# lb-charDisp-SMPS5V.net
KiCad netlist of a schematic drawn in Altium Designer
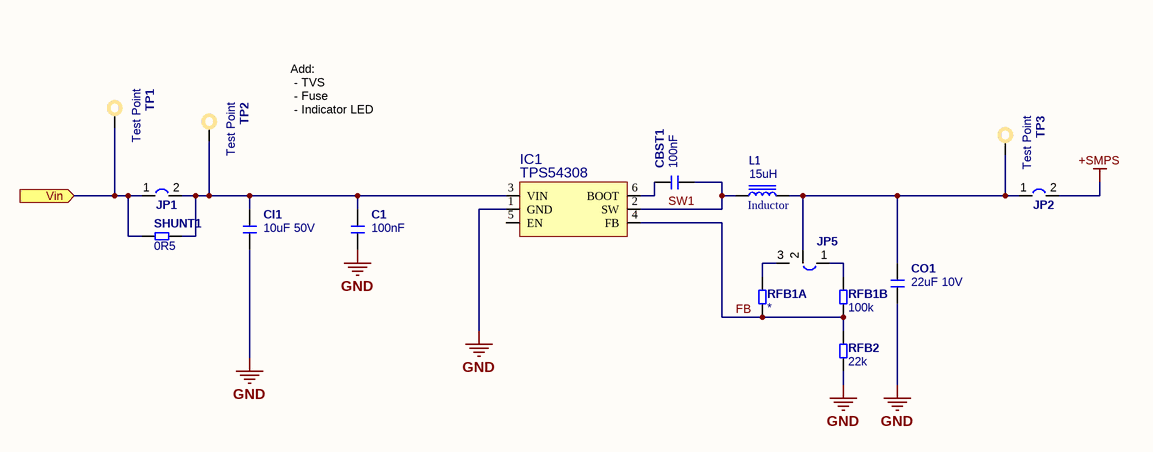
[diagram p0: lb-charDisp-SMPS5V.SchDoc]

(export (version "E")
  (design (tool "Eeschema 10.0.6"))
  (components
    (comp (ref "C1")
      (value "100nF")
      (footprint "C0603_N")
      (description "Capacitor MLCC")
      (fields
        (field (name "MANUFACTURER") "Yageo")
        (field (name "MANUFACTURER PART NUMBER") "CC0603KRX7R9BB104")
      )
      (libsource (lib "wes") (part "Capacitor"))
    )
    (comp (ref "CBST1")
      (value "100nF")
      (footprint "C0603_N")
      (description "Capacitor MLCC")
      (fields
        (field (name "MANUFACTURER") "Yageo")
        (field (name "MANUFACTURER PART NUMBER") "CC0603KRX7R9BB104")
      )
      (libsource (lib "wes") (part "Capacitor"))
    )
    (comp (ref "CI1")
      (value "10uF 50V")
      (footprint "C1210_N")
      (description "Capacitor MLCC")
      (fields
        (field (name "MANUFACTURER") "Yageo")
        (field (name "MANUFACTURER PART NUMBER") "CC0603KRX7R9BB104")
      )
      (libsource (lib "wes") (part "Capacitor"))
    )
    (comp (ref "CO1")
      (value "22uF 10V")
      (footprint "C1210_N")
      (description "Capacitor MLCC")
      (fields
        (field (name "MANUFACTURER") "Yageo")
        (field (name "MANUFACTURER PART NUMBER") "CC0603KRX7R9BB104")
      )
      (libsource (lib "wes") (part "Capacitor"))
    )
    (comp (ref "IC1")
      (value "TPS54308")
      (footprint "SOT23")
      (description "Buck Converter")
      (libsource (lib "wes") (part "TPS54308"))
    )
    (comp (ref "JP1")
      (value "Jumper 2W")
      (footprint "Jumper SMD 2W NO")
      (libsource (lib "wes") (part "Jumper 2W"))
    )
    (comp (ref "JP2")
      (value "Jumper 2W")
      (footprint "Jumper SMD 2W NO")
      (libsource (lib "wes") (part "Jumper 2W"))
    )
    (comp (ref "JP5")
      (value "Jumper 3W")
      (footprint "Jumper SMD 3W NO")
      (libsource (lib "wes") (part "Jumper 3W"))
    )
    (comp (ref "L1")
      (value "Inductor")
      (footprint "Inductor 4mm")
      (fields (field (name "ALTIUM_VALUE") "15uH"))
      (libsource (lib "wes") (part "Inductor"))
    )
    (comp (ref "RFB1A")
      (value "*")
      (footprint "R0603")
      (fields (field (name "ALTIUM_VALUE") "*") (field (name "PUBLISHER") "Altium Limited"))
      (libsource (lib "wes") (part "Resistor"))
    )
    (comp (ref "RFB1B")
      (value "100k")
      (footprint "R0603")
      (fields (field (name "PUBLISHER") "Altium Limited"))
      (libsource (lib "wes") (part "Resistor"))
    )
    (comp (ref "RFB2")
      (value "22k")
      (footprint "R0603")
      (fields (field (name "PUBLISHER") "Altium Limited"))
      (libsource (lib "wes") (part "Resistor"))
    )
    (comp (ref "SHUNT1")
      (value "0R5")
      (footprint "R0603")
      (fields (field (name "PUBLISHER") "Altium Limited"))
      (libsource (lib "wes") (part "Resistor"))
    )
    (comp (ref "TP1")
      (value "Test Point")
      (footprint "TestPoint-1.2mm")
      (libsource (lib "wes") (part "Test Point"))
    )
    (comp (ref "TP2")
      (value "Test Point")
      (footprint "TestPoint-1.2mm")
      (libsource (lib "wes") (part "Test Point"))
    )
    (comp (ref "TP3")
      (value "Test Point")
      (footprint "TestPoint-1.2mm")
      (libsource (lib "wes") (part "Test Point"))
    )
  )
  (nets
    (net (code "1") (name "+SMPS") (class "Default")
      (node (ref "JP2") (pin "2") (pinfunction "2_2") (pintype "passive"))
    )
    (net (code "2") (name "/FB") (class "Default")
      (node (ref "IC1") (pin "4") (pinfunction "FB_4") (pintype "passive"))
      (node (ref "RFB1A") (pin "1") (pinfunction "1_1") (pintype "passive"))
      (node (ref "RFB1B") (pin "1") (pinfunction "1_1") (pintype "passive"))
      (node (ref "RFB2") (pin "2") (pinfunction "2_2") (pintype "passive"))
    )
    (net (code "3") (name "/SW1") (class "Default")
      (node (ref "CBST1") (pin "2") (pintype "passive"))
      (node (ref "IC1") (pin "2") (pinfunction "SW_2") (pintype "passive"))
      (node (ref "L1") (pin "1") (pinfunction "1_1") (pintype "passive"))
    )
    (net (code "4") (name "/Vin") (class "Default")
      (node (ref "JP1") (pin "1") (pinfunction "1_1") (pintype "passive"))
      (node (ref "SHUNT1") (pin "1") (pinfunction "1_1") (pintype "passive"))
      (node (ref "TP1") (pin "1") (pinfunction "1_1") (pintype "passive"))
    )
    (net (code "5") (name "GND") (class "Default")
      (node (ref "C1") (pin "2") (pintype "passive"))
      (node (ref "CI1") (pin "2") (pintype "passive"))
      (node (ref "CO1") (pin "2") (pintype "passive"))
      (node (ref "IC1") (pin "1") (pinfunction "GND_1") (pintype "passive"))
      (node (ref "RFB2") (pin "1") (pinfunction "1_1") (pintype "passive"))
    )
    (net (code "6") (name "Net-(CO1-Pad1)") (class "Default")
      (node (ref "CO1") (pin "1") (pintype "passive"))
      (node (ref "JP2") (pin "1") (pinfunction "1_1") (pintype "passive"))
      (node (ref "JP5") (pin "2") (pinfunction "2_2") (pintype "passive"))
      (node (ref "L1") (pin "2") (pinfunction "2_2") (pintype "passive"))
      (node (ref "TP3") (pin "1") (pinfunction "1_1") (pintype "passive"))
    )
    (net (code "7") (name "Net-(IC1-BOOT)") (class "Default")
      (node (ref "CBST1") (pin "1") (pintype "passive"))
      (node (ref "IC1") (pin "6") (pinfunction "BOOT_6") (pintype "passive"))
    )
    (net (code "8") (name "Net-(IC1-VIN)") (class "Default")
      (node (ref "C1") (pin "1") (pintype "passive"))
      (node (ref "CI1") (pin "1") (pintype "passive"))
      (node (ref "IC1") (pin "3") (pinfunction "VIN_3") (pintype "passive"))
      (node (ref "JP1") (pin "2") (pinfunction "2_2") (pintype "passive"))
      (node (ref "SHUNT1") (pin "2") (pinfunction "2_2") (pintype "passive"))
      (node (ref "TP2") (pin "1") (pinfunction "1_1") (pintype "passive"))
    )
    (net (code "9") (name "Net-(JP5-Pad1)") (class "Default")
      (node (ref "JP5") (pin "1") (pinfunction "1_1") (pintype "passive"))
      (node (ref "RFB1B") (pin "2") (pinfunction "2_2") (pintype "passive"))
    )
    (net (code "10") (name "Net-(JP5-Pad3)") (class "Default")
      (node (ref "JP5") (pin "3") (pinfunction "3_3") (pintype "passive"))
      (node (ref "RFB1A") (pin "2") (pinfunction "2_2") (pintype "passive"))
    )
    (net (code "11") (name "unconnected-(IC1-EN-Pad5)") (class "Default")
      (node (ref "IC1") (pin "5") (pinfunction "EN_5") (pintype "passive"))
    )
  )
)
